# uppsense.net
KiCad netlist of a schematic drawn in Altium Designer
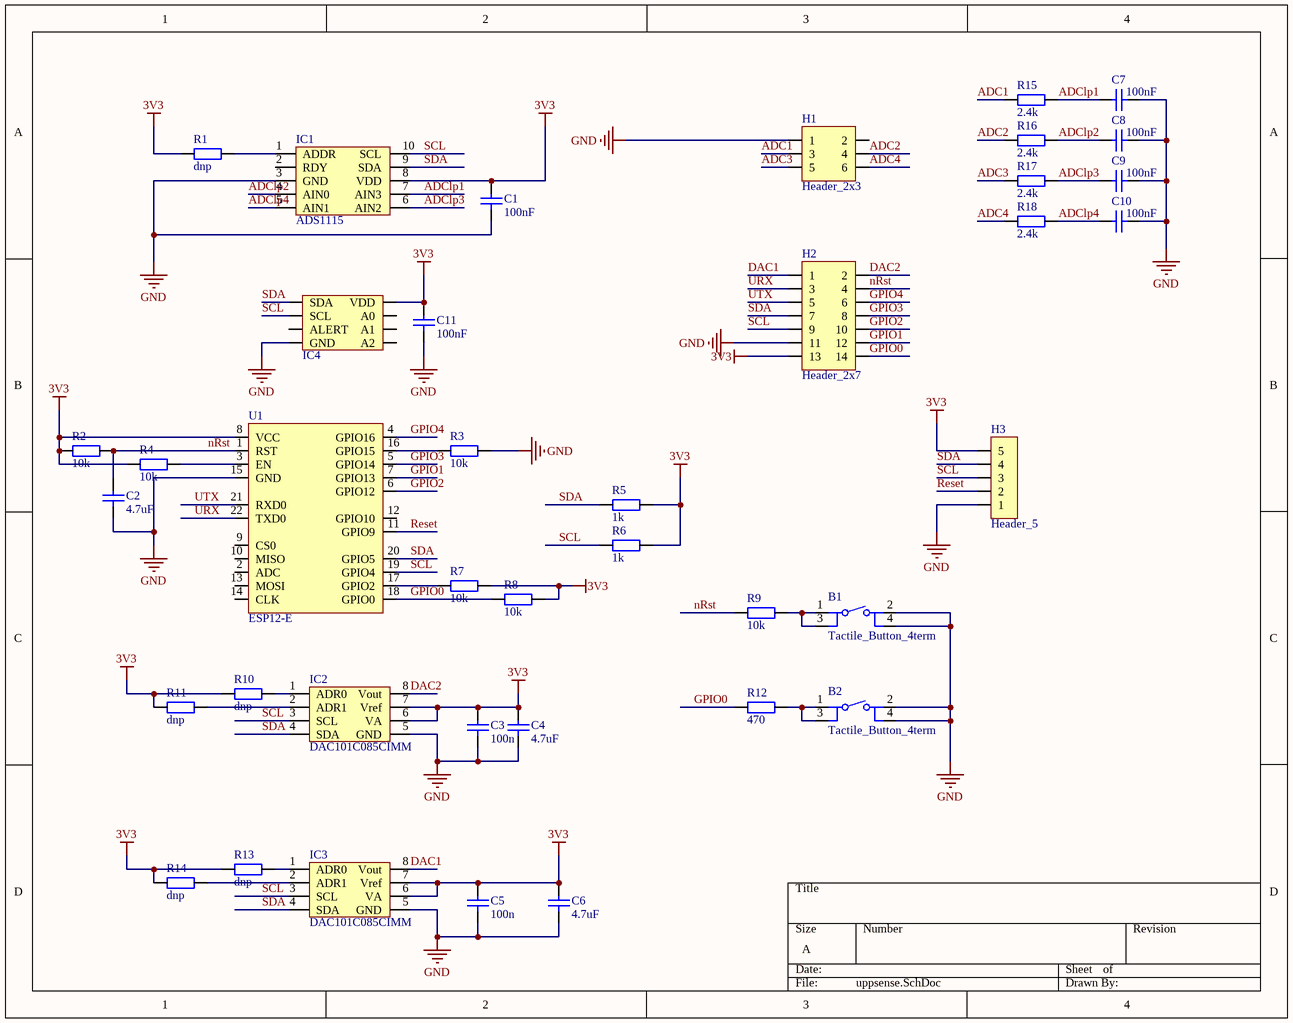
[diagram p0: uppsense.SchDoc]

(export (version "E")
  (design (tool "Eeschema 10.0.6"))
  (components
    (comp (ref "B1")
      (value "Tactile_Button_4term")
      (footprint "TACTILE_MINATUE_SMD_6x6mm")
      (libsource (lib "AranCustomFootprints") (part "Tactile_Button_4term"))
    )
    (comp (ref "B2")
      (value "Tactile_Button_4term")
      (footprint "TACTILE_MINATUE_SMD_6x6mm")
      (libsource (lib "AranCustomFootprints") (part "Tactile_Button_4term"))
    )
    (comp (ref "C1")
      (value "100nF")
      (footprint "C0603")
      (description "Schematic symbol of a capacitor")
      (libsource (lib "AranCustomFootprints") (part "Capacitor"))
    )
    (comp (ref "C2")
      (value "4.7uF")
      (footprint "C0603")
      (description "Schematic symbol of a capacitor")
      (libsource (lib "AranCustomFootprints") (part "Capacitor"))
    )
    (comp (ref "C3")
      (value "100n")
      (footprint "C0603")
      (description "Schematic symbol of a capacitor")
      (libsource (lib "AranCustomFootprints") (part "Capacitor"))
    )
    (comp (ref "C4")
      (value "4.7uF")
      (footprint "C0603")
      (description "Schematic symbol of a capacitor")
      (libsource (lib "AranCustomFootprints") (part "Capacitor"))
    )
    (comp (ref "C5")
      (value "100n")
      (footprint "C0603")
      (description "Schematic symbol of a capacitor")
      (libsource (lib "AranCustomFootprints") (part "Capacitor"))
    )
    (comp (ref "C6")
      (value "4.7uF")
      (footprint "C0603")
      (description "Schematic symbol of a capacitor")
      (libsource (lib "AranCustomFootprints") (part "Capacitor"))
    )
    (comp (ref "C7")
      (value "100nF")
      (footprint "C0603")
      (description "Schematic symbol of a capacitor")
      (libsource (lib "AranCustomFootprints") (part "Capacitor"))
    )
    (comp (ref "C8")
      (value "100nF")
      (footprint "C0603")
      (description "Schematic symbol of a capacitor")
      (libsource (lib "AranCustomFootprints") (part "Capacitor"))
    )
    (comp (ref "C9")
      (value "100nF")
      (footprint "C0603")
      (description "Schematic symbol of a capacitor")
      (libsource (lib "AranCustomFootprints") (part "Capacitor"))
    )
    (comp (ref "C10")
      (value "100nF")
      (footprint "C0603")
      (description "Schematic symbol of a capacitor")
      (libsource (lib "AranCustomFootprints") (part "Capacitor"))
    )
    (comp (ref "C11")
      (value "100nF")
      (footprint "C0603")
      (description "Schematic symbol of a capacitor")
      (libsource (lib "AranCustomFootprints") (part "Capacitor"))
    )
    (comp (ref "H1")
      (value "Header_2x3")
      (footprint "HEADER_MALE_2x3_RIGHT_ANGLE")
      (description "Generic 6pin header symbol")
      (libsource (lib "elmarlib") (part "Header_2x3"))
    )
    (comp (ref "H2")
      (value "Header_2x7")
      (footprint "HEADER_MALE_2x7_RIGHT_ANGLE")
      (description "Generic 14pin header symbol")
      (libsource (lib "elmarlib") (part "Header_2x7"))
    )
    (comp (ref "H3")
      (value "Header_5")
      (footprint "Header_MALE_0.05INCH_5")
      (description "Generic 5pin header symbol")
      (libsource (lib "AranCustomFootprints") (part "Header_5"))
    )
    (comp (ref "IC1")
      (value "ADS1115")
      (footprint "10-VSSOP-0.5")
      (description "ADS111x  Ultra-Small,  Low-Power,  I  2  C-Compatible,  860-SPS,  16-Bit  ADCs")
      (libsource (lib "elmarlib") (part "ADS1115"))
    )
    (comp (ref "IC2")
      (value "DAC101C085CIMM")
      (footprint "8-VSSOP")
      (libsource (lib "elmarlib") (part "DAC101C085CIMM"))
    )
    (comp (ref "IC3")
      (value "DAC101C085CIMM")
      (footprint "8-VSSOP")
      (libsource (lib "elmarlib") (part "DAC101C085CIMM"))
    )
    (comp (ref "IC4")
      (value "MCP9808")
      (footprint "8-MSOP")
      (description "v±0.5°C Maximum Accuracy   Digital Temperature Sensor")
      (libsource (lib "elmarlib") (part "MCP9808"))
    )
    (comp (ref "R1")
      (value "dnp")
      (footprint "R0603")
      (description "Schematic symbol of a resistor")
      (libsource (lib "AranCustomFootprints") (part "Resistor"))
    )
    (comp (ref "R2")
      (value "10k")
      (footprint "R0603")
      (description "Schematic symbol of a resistor")
      (libsource (lib "AranCustomFootprints") (part "Resistor"))
    )
    (comp (ref "R3")
      (value "10k")
      (footprint "R0603")
      (description "Schematic symbol of a resistor")
      (libsource (lib "AranCustomFootprints") (part "Resistor"))
    )
    (comp (ref "R4")
      (value "10k")
      (footprint "R0603")
      (description "Schematic symbol of a resistor")
      (libsource (lib "AranCustomFootprints") (part "Resistor"))
    )
    (comp (ref "R5")
      (value "1k")
      (footprint "R0603")
      (description "Schematic symbol of a resistor")
      (libsource (lib "AranCustomFootprints") (part "Resistor"))
    )
    (comp (ref "R6")
      (value "1k")
      (footprint "R0603")
      (description "Schematic symbol of a resistor")
      (libsource (lib "AranCustomFootprints") (part "Resistor"))
    )
    (comp (ref "R7")
      (value "10k")
      (footprint "R0603")
      (description "Schematic symbol of a resistor")
      (libsource (lib "AranCustomFootprints") (part "Resistor"))
    )
    (comp (ref "R8")
      (value "10k")
      (footprint "R0603")
      (description "Schematic symbol of a resistor")
      (libsource (lib "AranCustomFootprints") (part "Resistor"))
    )
    (comp (ref "R9")
      (value "10k")
      (footprint "R0603")
      (description "Schematic symbol of a resistor")
      (libsource (lib "AranCustomFootprints") (part "Resistor"))
    )
    (comp (ref "R10")
      (value "dnp")
      (footprint "R0603")
      (description "Schematic symbol of a resistor")
      (libsource (lib "AranCustomFootprints") (part "Resistor"))
    )
    (comp (ref "R11")
      (value "dnp")
      (footprint "R0603")
      (description "Schematic symbol of a resistor")
      (libsource (lib "AranCustomFootprints") (part "Resistor"))
    )
    (comp (ref "R12")
      (value "470")
      (footprint "R0603")
      (description "Schematic symbol of a resistor")
      (libsource (lib "AranCustomFootprints") (part "Resistor"))
    )
    (comp (ref "R13")
      (value "dnp")
      (footprint "R0603")
      (description "Schematic symbol of a resistor")
      (libsource (lib "AranCustomFootprints") (part "Resistor"))
    )
    (comp (ref "R14")
      (value "dnp")
      (footprint "R0603")
      (description "Schematic symbol of a resistor")
      (libsource (lib "AranCustomFootprints") (part "Resistor"))
    )
    (comp (ref "R15")
      (value "2.4k")
      (footprint "R0603")
      (description "Schematic symbol of a resistor")
      (libsource (lib "AranCustomFootprints") (part "Resistor"))
    )
    (comp (ref "R16")
      (value "2.4k")
      (footprint "R0603")
      (description "Schematic symbol of a resistor")
      (libsource (lib "AranCustomFootprints") (part "Resistor"))
    )
    (comp (ref "R17")
      (value "2.4k")
      (footprint "R0603")
      (description "Schematic symbol of a resistor")
      (libsource (lib "AranCustomFootprints") (part "Resistor"))
    )
    (comp (ref "R18")
      (value "2.4k")
      (footprint "R0603")
      (description "Schematic symbol of a resistor")
      (libsource (lib "AranCustomFootprints") (part "Resistor"))
    )
    (comp (ref "U1") (value "ESP12-E") (footprint "ESP12-E") (libsource (lib "elmarlib") (part "ESP12-E")))
  )
  (nets
    (net (code "1") (name "/ADC1") (class "Default")
      (node (ref "H1") (pin "3") (pinfunction "3_3") (pintype "passive"))
      (node (ref "R15") (pin "2") (pinfunction "2_2") (pintype "passive"))
    )
    (net (code "2") (name "/ADC2") (class "Default")
      (node (ref "H1") (pin "4") (pinfunction "4_4") (pintype "passive"))
      (node (ref "R16") (pin "2") (pinfunction "2_2") (pintype "passive"))
    )
    (net (code "3") (name "/ADC3") (class "Default")
      (node (ref "H1") (pin "5") (pinfunction "5_5") (pintype "passive"))
      (node (ref "R17") (pin "2") (pinfunction "2_2") (pintype "passive"))
    )
    (net (code "4") (name "/ADC4") (class "Default")
      (node (ref "H1") (pin "6") (pinfunction "6_6") (pintype "passive"))
      (node (ref "R18") (pin "2") (pinfunction "2_2") (pintype "passive"))
    )
    (net (code "5") (name "/ADClp1") (class "Default")
      (node (ref "C7") (pin "1") (pinfunction "1_1") (pintype "passive"))
      (node (ref "IC1") (pin "7") (pinfunction "AIN3_7") (pintype "passive"))
      (node (ref "R15") (pin "1") (pinfunction "1_1") (pintype "passive"))
    )
    (net (code "6") (name "/ADClp2") (class "Default")
      (node (ref "C8") (pin "1") (pinfunction "1_1") (pintype "passive"))
      (node (ref "IC1") (pin "4") (pinfunction "AIN0_4") (pintype "passive"))
      (node (ref "R16") (pin "1") (pinfunction "1_1") (pintype "passive"))
    )
    (net (code "7") (name "/ADClp3") (class "Default")
      (node (ref "C9") (pin "1") (pinfunction "1_1") (pintype "passive"))
      (node (ref "IC1") (pin "6") (pinfunction "AIN2_6") (pintype "passive"))
      (node (ref "R17") (pin "1") (pinfunction "1_1") (pintype "passive"))
    )
    (net (code "8") (name "/ADClp4") (class "Default")
      (node (ref "C10") (pin "1") (pinfunction "1_1") (pintype "passive"))
      (node (ref "IC1") (pin "5") (pinfunction "AIN1_5") (pintype "passive"))
      (node (ref "R18") (pin "1") (pinfunction "1_1") (pintype "passive"))
    )
    (net (code "9") (name "/DAC1") (class "Default")
      (node (ref "H2") (pin "1") (pinfunction "1_1") (pintype "passive"))
      (node (ref "IC3") (pin "8") (pinfunction "Vout_8") (pintype "passive"))
    )
    (net (code "10") (name "/DAC2") (class "Default")
      (node (ref "H2") (pin "2") (pinfunction "2_2") (pintype "passive"))
      (node (ref "IC2") (pin "8") (pinfunction "Vout_8") (pintype "passive"))
    )
    (net (code "11") (name "/GPIO0") (class "Default")
      (node (ref "H2") (pin "14") (pinfunction "14_14") (pintype "passive"))
      (node (ref "R12") (pin "2") (pinfunction "2_2") (pintype "passive"))
      (node (ref "R8") (pin "2") (pinfunction "2_2") (pintype "passive"))
      (node (ref "U1") (pin "18") (pinfunction "GPIO0_18") (pintype "passive"))
    )
    (net (code "12") (name "/GPIO1") (class "Default")
      (node (ref "H2") (pin "12") (pinfunction "12_12") (pintype "passive"))
      (node (ref "U1") (pin "7") (pinfunction "GPIO13_7") (pintype "passive"))
    )
    (net (code "13") (name "/GPIO2") (class "Default")
      (node (ref "H2") (pin "10") (pinfunction "10_10") (pintype "passive"))
      (node (ref "U1") (pin "6") (pinfunction "GPIO12_6") (pintype "passive"))
    )
    (net (code "14") (name "/GPIO3") (class "Default")
      (node (ref "H2") (pin "8") (pinfunction "8_8") (pintype "passive"))
      (node (ref "U1") (pin "5") (pinfunction "GPIO14_5") (pintype "passive"))
    )
    (net (code "15") (name "/GPIO4") (class "Default")
      (node (ref "H2") (pin "6") (pinfunction "6_6") (pintype "passive"))
      (node (ref "U1") (pin "4") (pinfunction "GPIO16_4") (pintype "passive"))
    )
    (net (code "16") (name "/Reset") (class "Default")
      (node (ref "H3") (pin "2") (pinfunction "2_2") (pintype "passive"))
      (node (ref "U1") (pin "11") (pinfunction "GPIO9_11") (pintype "passive"))
    )
    (net (code "17") (name "/SCL") (class "Default")
      (node (ref "H2") (pin "9") (pinfunction "9_9") (pintype "passive"))
      (node (ref "H3") (pin "3") (pinfunction "3_3") (pintype "passive"))
      (node (ref "IC1") (pin "10") (pinfunction "SCL_10") (pintype "passive"))
      (node (ref "IC2") (pin "3") (pinfunction "SCL_3") (pintype "passive"))
      (node (ref "IC3") (pin "3") (pinfunction "SCL_3") (pintype "passive"))
      (node (ref "IC4") (pin "2") (pinfunction "SCL_2") (pintype "passive"))
      (node (ref "R6") (pin "2") (pinfunction "2_2") (pintype "passive"))
      (node (ref "U1") (pin "19") (pinfunction "GPIO4_19") (pintype "passive"))
    )
    (net (code "18") (name "/SDA") (class "Default")
      (node (ref "H2") (pin "7") (pinfunction "7_7") (pintype "passive"))
      (node (ref "H3") (pin "4") (pinfunction "4_4") (pintype "passive"))
      (node (ref "IC1") (pin "9") (pinfunction "SDA_9") (pintype "passive"))
      (node (ref "IC2") (pin "4") (pinfunction "SDA_4") (pintype "passive"))
      (node (ref "IC3") (pin "4") (pinfunction "SDA_4") (pintype "passive"))
      (node (ref "IC4") (pin "1") (pinfunction "SDA_1") (pintype "passive"))
      (node (ref "R5") (pin "2") (pinfunction "2_2") (pintype "passive"))
      (node (ref "U1") (pin "20") (pinfunction "GPIO5_20") (pintype "passive"))
    )
    (net (code "19") (name "/URX") (class "Default")
      (node (ref "H2") (pin "3") (pinfunction "3_3") (pintype "passive"))
      (node (ref "U1") (pin "22") (pinfunction "TXD0_22") (pintype "passive"))
    )
    (net (code "20") (name "/UTX") (class "Default")
      (node (ref "H2") (pin "5") (pinfunction "5_5") (pintype "passive"))
      (node (ref "U1") (pin "21") (pinfunction "RXD0_21") (pintype "passive"))
    )
    (net (code "21") (name "/nRst") (class "Default")
      (node (ref "C2") (pin "1") (pinfunction "1_1") (pintype "passive"))
      (node (ref "H2") (pin "4") (pinfunction "4_4") (pintype "passive"))
      (node (ref "R2") (pin "1") (pinfunction "1_1") (pintype "passive"))
      (node (ref "R9") (pin "2") (pinfunction "2_2") (pintype "passive"))
      (node (ref "U1") (pin "1") (pinfunction "RST_1") (pintype "passive"))
    )
    (net (code "22") (name "3V3") (class "Default")
      (node (ref "C1") (pin "1") (pinfunction "1_1") (pintype "passive"))
      (node (ref "C11") (pin "1") (pinfunction "1_1") (pintype "passive"))
      (node (ref "C3") (pin "1") (pinfunction "1_1") (pintype "passive"))
      (node (ref "C4") (pin "1") (pinfunction "1_1") (pintype "passive"))
      (node (ref "C5") (pin "1") (pinfunction "1_1") (pintype "passive"))
      (node (ref "C6") (pin "1") (pinfunction "1_1") (pintype "passive"))
      (node (ref "H2") (pin "13") (pinfunction "13_13") (pintype "passive"))
      (node (ref "H3") (pin "5") (pinfunction "5_5") (pintype "passive"))
      (node (ref "IC1") (pin "8") (pinfunction "VDD_8") (pintype "passive"))
      (node (ref "IC2") (pin "6") (pinfunction "VA_6") (pintype "passive"))
      (node (ref "IC2") (pin "7") (pinfunction "Vref_7") (pintype "passive"))
      (node (ref "IC3") (pin "6") (pinfunction "VA_6") (pintype "passive"))
      (node (ref "IC3") (pin "7") (pinfunction "Vref_7") (pintype "passive"))
      (node (ref "IC4") (pin "8") (pinfunction "VDD_8") (pintype "passive"))
      (node (ref "R1") (pin "2") (pinfunction "2_2") (pintype "passive"))
      (node (ref "R10") (pin "2") (pinfunction "2_2") (pintype "passive"))
      (node (ref "R11") (pin "2") (pinfunction "2_2") (pintype "passive"))
      (node (ref "R13") (pin "2") (pinfunction "2_2") (pintype "passive"))
      (node (ref "R14") (pin "2") (pinfunction "2_2") (pintype "passive"))
      (node (ref "R2") (pin "2") (pinfunction "2_2") (pintype "passive"))
      (node (ref "R4") (pin "2") (pinfunction "2_2") (pintype "passive"))
      (node (ref "R5") (pin "1") (pinfunction "1_1") (pintype "passive"))
      (node (ref "R6") (pin "1") (pinfunction "1_1") (pintype "passive"))
      (node (ref "R7") (pin "1") (pinfunction "1_1") (pintype "passive"))
      (node (ref "R8") (pin "1") (pinfunction "1_1") (pintype "passive"))
      (node (ref "U1") (pin "8") (pinfunction "VCC_8") (pintype "passive"))
    )
    (net (code "23") (name "GND") (class "Default")
      (node (ref "B1") (pin "2") (pintype "passive"))
      (node (ref "B1") (pin "4") (pintype "passive"))
      (node (ref "B2") (pin "2") (pintype "passive"))
      (node (ref "B2") (pin "4") (pintype "passive"))
      (node (ref "C1") (pin "2") (pinfunction "2_2") (pintype "passive"))
      (node (ref "C10") (pin "2") (pinfunction "2_2") (pintype "passive"))
      (node (ref "C11") (pin "2") (pinfunction "2_2") (pintype "passive"))
      (node (ref "C2") (pin "2") (pinfunction "2_2") (pintype "passive"))
      (node (ref "C3") (pin "2") (pinfunction "2_2") (pintype "passive"))
      (node (ref "C4") (pin "2") (pinfunction "2_2") (pintype "passive"))
      (node (ref "C5") (pin "2") (pinfunction "2_2") (pintype "passive"))
      (node (ref "C6") (pin "2") (pinfunction "2_2") (pintype "passive"))
      (node (ref "C7") (pin "2") (pinfunction "2_2") (pintype "passive"))
      (node (ref "C8") (pin "2") (pinfunction "2_2") (pintype "passive"))
      (node (ref "C9") (pin "2") (pinfunction "2_2") (pintype "passive"))
      (node (ref "H1") (pin "1") (pinfunction "1_1") (pintype "passive"))
      (node (ref "H2") (pin "11") (pinfunction "11_11") (pintype "passive"))
      (node (ref "H3") (pin "1") (pinfunction "1_1") (pintype "passive"))
      (node (ref "IC1") (pin "3") (pinfunction "GND_3") (pintype "passive"))
      (node (ref "IC2") (pin "5") (pinfunction "GND_5") (pintype "passive"))
      (node (ref "IC3") (pin "5") (pinfunction "GND_5") (pintype "passive"))
      (node (ref "IC4") (pin "4") (pinfunction "GND_4") (pintype "passive"))
      (node (ref "R3") (pin "1") (pinfunction "1_1") (pintype "passive"))
      (node (ref "U1") (pin "15") (pinfunction "GND_15") (pintype "passive"))
    )
    (net (code "24") (name "Net-(B1-Pad1)") (class "Default")
      (node (ref "B1") (pin "1") (pintype "passive"))
      (node (ref "B1") (pin "3") (pintype "passive"))
      (node (ref "R9") (pin "1") (pinfunction "1_1") (pintype "passive"))
    )
    (net (code "25") (name "Net-(B2-Pad1)") (class "Default")
      (node (ref "B2") (pin "1") (pintype "passive"))
      (node (ref "B2") (pin "3") (pintype "passive"))
      (node (ref "R12") (pin "1") (pinfunction "1_1") (pintype "passive"))
    )
    (net (code "26") (name "Net-(IC1-ADDR)") (class "Default")
      (node (ref "IC1") (pin "1") (pinfunction "ADDR_1") (pintype "passive"))
      (node (ref "R1") (pin "1") (pinfunction "1_1") (pintype "passive"))
    )
    (net (code "27") (name "Net-(IC2-ADR0)") (class "Default")
      (node (ref "IC2") (pin "1") (pinfunction "ADR0_1") (pintype "passive"))
      (node (ref "R10") (pin "1") (pinfunction "1_1") (pintype "passive"))
    )
    (net (code "28") (name "Net-(IC2-ADR1)") (class "Default")
      (node (ref "IC2") (pin "2") (pinfunction "ADR1_2") (pintype "passive"))
      (node (ref "R11") (pin "1") (pinfunction "1_1") (pintype "passive"))
    )
    (net (code "29") (name "Net-(IC3-ADR0)") (class "Default")
      (node (ref "IC3") (pin "1") (pinfunction "ADR0_1") (pintype "passive"))
      (node (ref "R13") (pin "1") (pinfunction "1_1") (pintype "passive"))
    )
    (net (code "30") (name "Net-(IC3-ADR1)") (class "Default")
      (node (ref "IC3") (pin "2") (pinfunction "ADR1_2") (pintype "passive"))
      (node (ref "R14") (pin "1") (pinfunction "1_1") (pintype "passive"))
    )
    (net (code "31") (name "Net-(U1-EN)") (class "Default")
      (node (ref "R4") (pin "1") (pinfunction "1_1") (pintype "passive"))
      (node (ref "U1") (pin "3") (pinfunction "EN_3") (pintype "passive"))
    )
    (net (code "32") (name "Net-(U1-GPIO2)") (class "Default")
      (node (ref "R7") (pin "2") (pinfunction "2_2") (pintype "passive"))
      (node (ref "U1") (pin "17") (pinfunction "GPIO2_17") (pintype "passive"))
    )
    (net (code "33") (name "Net-(U1-GPIO15)") (class "Default")
      (node (ref "R3") (pin "2") (pinfunction "2_2") (pintype "passive"))
      (node (ref "U1") (pin "16") (pinfunction "GPIO15_16") (pintype "passive"))
    )
    (net (code "34") (name "unconnected-(H1-Pad2)") (class "Default")
      (node (ref "H1") (pin "2") (pinfunction "2_2") (pintype "passive"))
    )
    (net (code "35") (name "unconnected-(IC1-RDY-Pad2)") (class "Default")
      (node (ref "IC1") (pin "2") (pinfunction "RDY_2") (pintype "passive"))
    )
    (net (code "36") (name "unconnected-(IC4-A0-Pad7)") (class "Default")
      (node (ref "IC4") (pin "7") (pinfunction "A0_7") (pintype "passive"))
    )
    (net (code "37") (name "unconnected-(IC4-A1-Pad6)") (class "Default")
      (node (ref "IC4") (pin "6") (pinfunction "A1_6") (pintype "passive"))
    )
    (net (code "38") (name "unconnected-(IC4-A2-Pad5)") (class "Default")
      (node (ref "IC4") (pin "5") (pinfunction "A2_5") (pintype "passive"))
    )
    (net (code "39") (name "unconnected-(IC4-ALERT-Pad3)") (class "Default")
      (node (ref "IC4") (pin "3") (pinfunction "ALERT_3") (pintype "passive"))
    )
    (net (code "40") (name "unconnected-(U1-ADC-Pad2)") (class "Default")
      (node (ref "U1") (pin "2") (pinfunction "ADC_2") (pintype "passive"))
    )
    (net (code "41") (name "unconnected-(U1-CLK-Pad14)") (class "Default")
      (node (ref "U1") (pin "14") (pinfunction "CLK_14") (pintype "passive"))
    )
    (net (code "42") (name "unconnected-(U1-CS0-Pad9)") (class "Default")
      (node (ref "U1") (pin "9") (pinfunction "CS0_9") (pintype "passive"))
    )
    (net (code "43") (name "unconnected-(U1-GPIO10-Pad12)") (class "Default")
      (node (ref "U1") (pin "12") (pinfunction "GPIO10_12") (pintype "passive"))
    )
    (net (code "44") (name "unconnected-(U1-MISO-Pad10)") (class "Default")
      (node (ref "U1") (pin "10") (pinfunction "MISO_10") (pintype "passive"))
    )
    (net (code "45") (name "unconnected-(U1-MOSI-Pad13)") (class "Default")
      (node (ref "U1") (pin "13") (pinfunction "MOSI_13") (pintype "passive"))
    )
  )
)
